# 8k.net
KiCad netlist of a schematic drawn in EAGLE
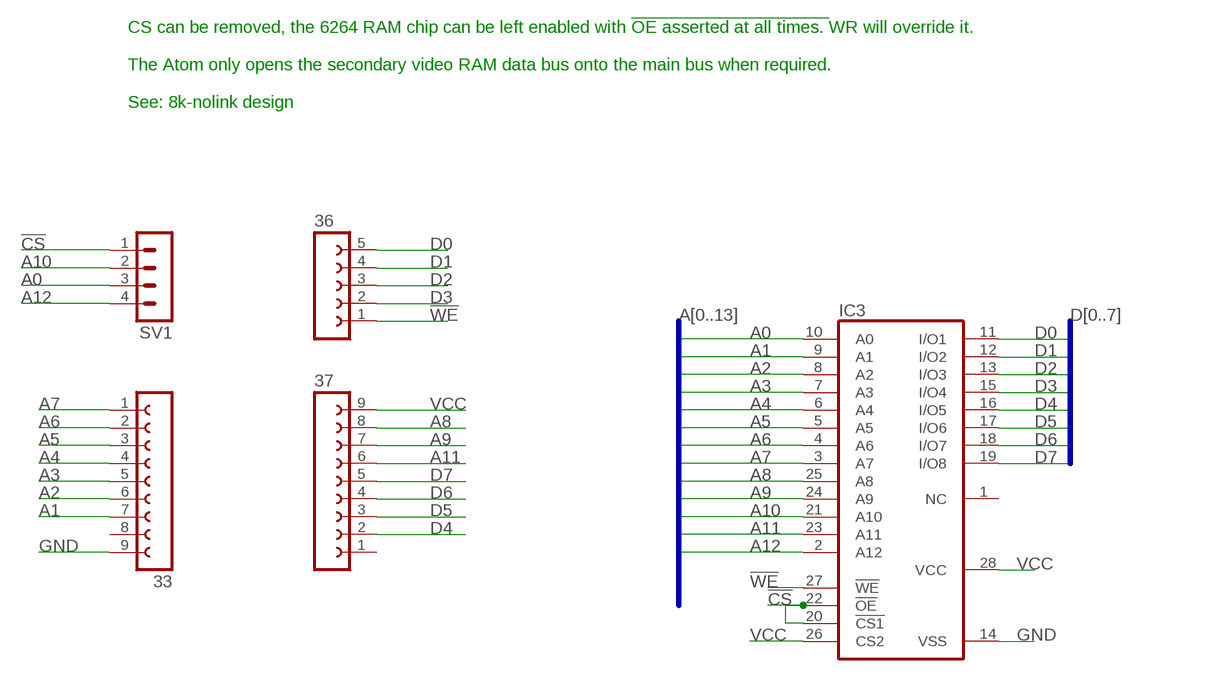
[diagram p0: schematic, sheet 1]

(export (version "E")
  (design (tool "Eeschema 10.0.6"))
  (components
    (comp (ref "33")
      (value "FE09-1")
      (footprint "eagle-import:FE09")
      (libsource (lib "eagle-import") (part "FE09-1"))
    )
    (comp (ref "36")
      (value "FE05-1")
      (footprint "eagle-import:FE05-1")
      (libsource (lib "eagle-import") (part "FE05-1"))
    )
    (comp (ref "37")
      (value "FE09-1")
      (footprint "eagle-import:FE09")
      (libsource (lib "eagle-import") (part "FE09-1"))
    )
    (comp (ref "IC3")
      (value "6264A")
      (footprint "eagle-import:DIL28-6")
      (libsource (lib "eagle-import") (part "6264A"))
    )
    (comp (ref "SV1")
      (value "MA04-1")
      (footprint "eagle-import:MA04-1")
      (libsource (lib "eagle-import") (part "MA04-1"))
    )
  )
  (nets
    (net (code "2") (name "/A0") (class "Default")
      (node (ref "IC3") (pin "10") (pinfunction "A0_10") (pintype "input"))
      (node (ref "SV1") (pin "3") (pinfunction "3_3") (pintype "passive"))
    )
    (net (code "3") (name "/A1") (class "Default")
      (node (ref "33") (pin "7") (pinfunction "7_7") (pintype "passive"))
      (node (ref "IC3") (pin "9") (pinfunction "A1_9") (pintype "input"))
    )
    (net (code "4") (name "/A2") (class "Default")
      (node (ref "33") (pin "6") (pinfunction "6_6") (pintype "passive"))
      (node (ref "IC3") (pin "8") (pinfunction "A2_8") (pintype "input"))
    )
    (net (code "5") (name "/A3") (class "Default")
      (node (ref "33") (pin "5") (pinfunction "5_5") (pintype "passive"))
      (node (ref "IC3") (pin "7") (pinfunction "A3_7") (pintype "input"))
    )
    (net (code "6") (name "/A4") (class "Default")
      (node (ref "33") (pin "4") (pinfunction "4_4") (pintype "passive"))
      (node (ref "IC3") (pin "6") (pinfunction "A4_6") (pintype "input"))
    )
    (net (code "7") (name "/A5") (class "Default")
      (node (ref "33") (pin "3") (pinfunction "3_3") (pintype "passive"))
      (node (ref "IC3") (pin "5") (pinfunction "A5_5") (pintype "input"))
    )
    (net (code "8") (name "/A6") (class "Default")
      (node (ref "33") (pin "2") (pinfunction "2_2") (pintype "passive"))
      (node (ref "IC3") (pin "4") (pinfunction "A6_4") (pintype "input"))
    )
    (net (code "9") (name "/A7") (class "Default")
      (node (ref "33") (pin "1") (pinfunction "1_1") (pintype "passive"))
      (node (ref "IC3") (pin "3") (pinfunction "A7_3") (pintype "input"))
    )
    (net (code "10") (name "/A8") (class "Default")
      (node (ref "37") (pin "8") (pinfunction "8_8") (pintype "passive"))
      (node (ref "IC3") (pin "25") (pinfunction "A8_25") (pintype "input"))
    )
    (net (code "11") (name "/A9") (class "Default")
      (node (ref "37") (pin "7") (pinfunction "7_7") (pintype "passive"))
      (node (ref "IC3") (pin "24") (pinfunction "A9_24") (pintype "input"))
    )
    (net (code "12") (name "/A10") (class "Default")
      (node (ref "IC3") (pin "21") (pinfunction "A10_21") (pintype "input"))
      (node (ref "SV1") (pin "2") (pinfunction "2_2") (pintype "passive"))
    )
    (net (code "13") (name "/A11") (class "Default")
      (node (ref "37") (pin "6") (pinfunction "6_6") (pintype "passive"))
      (node (ref "IC3") (pin "23") (pinfunction "A11_23") (pintype "input"))
    )
    (net (code "14") (name "/A12") (class "Default")
      (node (ref "IC3") (pin "2") (pinfunction "A12_2") (pintype "input"))
      (node (ref "SV1") (pin "4") (pinfunction "4_4") (pintype "passive"))
    )
    (net (code "16") (name "/D0") (class "Default")
      (node (ref "36") (pin "5") (pinfunction "5_5") (pintype "passive"))
      (node (ref "IC3") (pin "11") (pinfunction "I/O1_11") (pintype "bidirectional"))
    )
    (net (code "17") (name "/D1") (class "Default")
      (node (ref "36") (pin "4") (pinfunction "4_4") (pintype "passive"))
      (node (ref "IC3") (pin "12") (pinfunction "I/O2_12") (pintype "bidirectional"))
    )
    (net (code "18") (name "/D2") (class "Default")
      (node (ref "36") (pin "3") (pinfunction "3_3") (pintype "passive"))
      (node (ref "IC3") (pin "13") (pinfunction "I/O3_13") (pintype "bidirectional"))
    )
    (net (code "19") (name "/D3") (class "Default")
      (node (ref "36") (pin "2") (pinfunction "2_2") (pintype "passive"))
      (node (ref "IC3") (pin "15") (pinfunction "I/O4_15") (pintype "bidirectional"))
    )
    (net (code "20") (name "/D4") (class "Default")
      (node (ref "37") (pin "2") (pinfunction "2_2") (pintype "passive"))
      (node (ref "IC3") (pin "16") (pinfunction "I/O5_16") (pintype "bidirectional"))
    )
    (net (code "21") (name "/D5") (class "Default")
      (node (ref "37") (pin "3") (pinfunction "3_3") (pintype "passive"))
      (node (ref "IC3") (pin "17") (pinfunction "I/O6_17") (pintype "bidirectional"))
    )
    (net (code "22") (name "/D6") (class "Default")
      (node (ref "37") (pin "4") (pinfunction "4_4") (pintype "passive"))
      (node (ref "IC3") (pin "18") (pinfunction "I/O7_18") (pintype "bidirectional"))
    )
    (net (code "23") (name "/D7") (class "Default")
      (node (ref "37") (pin "5") (pinfunction "5_5") (pintype "passive"))
      (node (ref "IC3") (pin "19") (pinfunction "I/O8_19") (pintype "bidirectional"))
    )
    (net (code "25") (name "/GND") (class "Default")
      (node (ref "33") (pin "9") (pinfunction "9_9") (pintype "passive"))
      (node (ref "IC3") (pin "14") (pinfunction "VSS_14") (pintype "power_in"))
    )
    (net (code "26") (name "/VCC") (class "Default")
      (node (ref "37") (pin "9") (pinfunction "9_9") (pintype "passive"))
      (node (ref "IC3") (pin "26") (pinfunction "CS2_26") (pintype "input"))
      (node (ref "IC3") (pin "28") (pinfunction "VCC_28") (pintype "power_in"))
    )
    (net (code "27") (name "/~{CS}") (class "Default")
      (node (ref "IC3") (pin "20") (pinfunction "~{CS1}_20") (pintype "input"))
      (node (ref "IC3") (pin "22") (pinfunction "~{OE}_22") (pintype "input"))
      (node (ref "SV1") (pin "1") (pinfunction "1_1") (pintype "passive"))
    )
    (net (code "28") (name "/~{WE}") (class "Default")
      (node (ref "36") (pin "1") (pinfunction "1_1") (pintype "passive"))
      (node (ref "IC3") (pin "27") (pinfunction "~{WE}_27") (pintype "input"))
    )
    (net (code "29") (name "unconnected-(33-Pad8)") (class "Default")
      (node (ref "33") (pin "8") (pinfunction "8_8") (pintype "passive"))
    )
    (net (code "30") (name "unconnected-(37-Pad1)") (class "Default")
      (node (ref "37") (pin "1") (pinfunction "1_1") (pintype "passive"))
    )
    (net (code "31") (name "unconnected-(IC3-NC-Pad1)") (class "Default")
      (node (ref "IC3") (pin "1") (pinfunction "NC_1") (pintype "no_connect"))
    )
  )
)
